# Main.net
KiCad netlist of a schematic drawn in Altium Designer
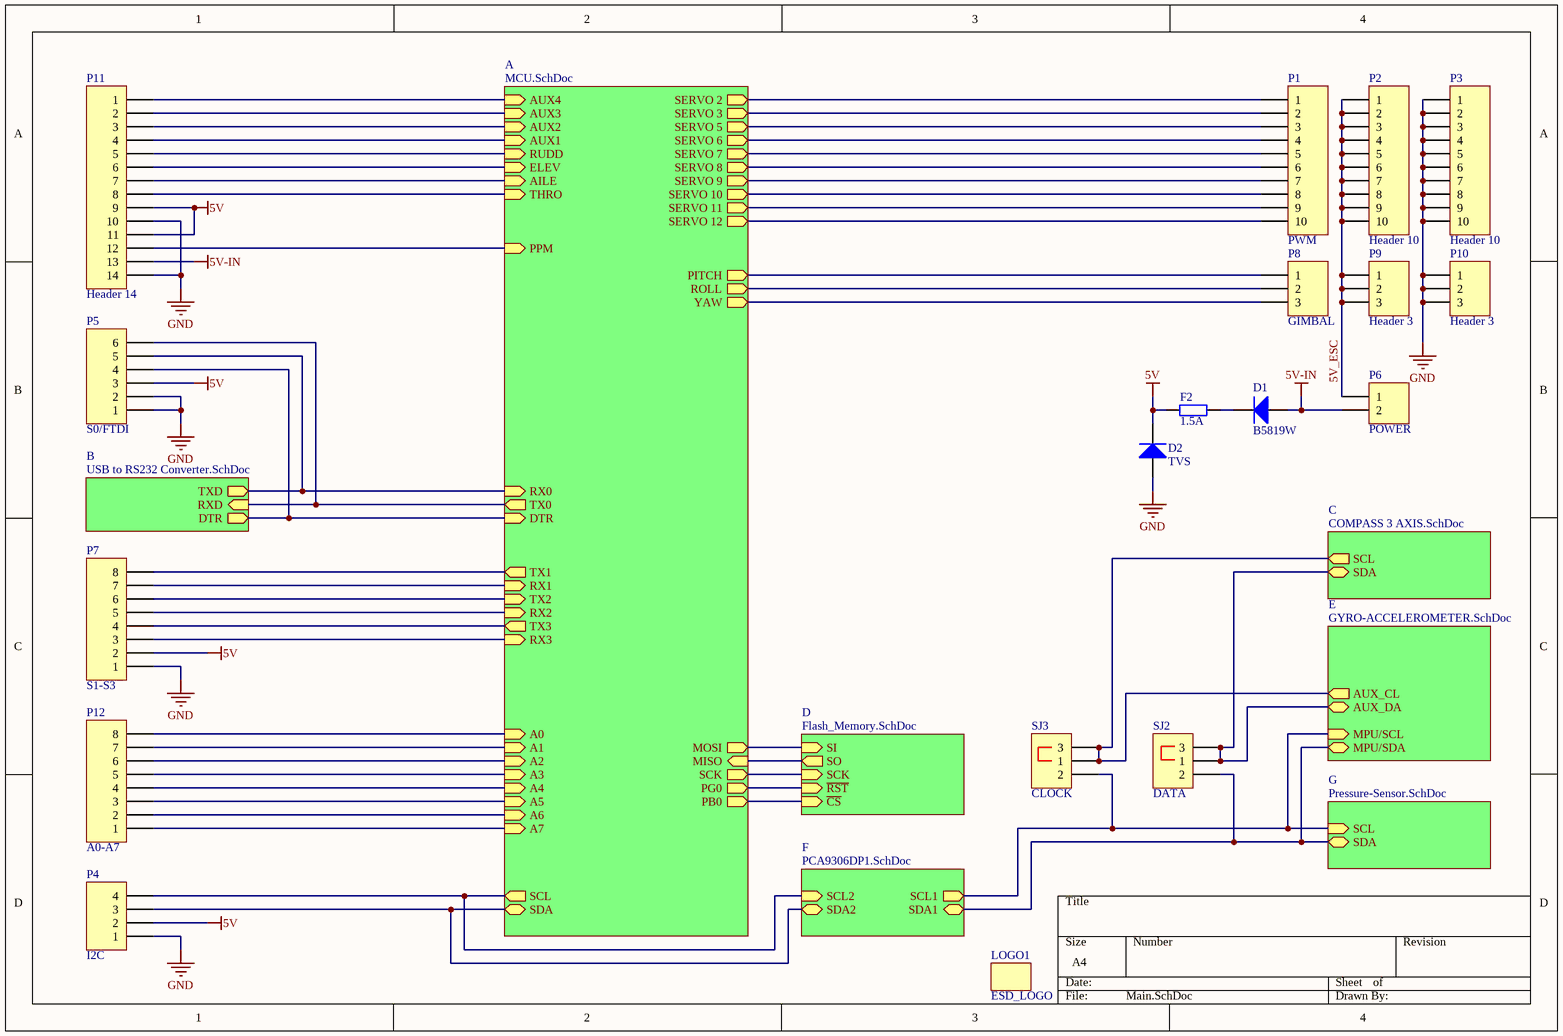
[diagram p0: Main.SchDoc]

(export (version "E")
  (design (tool "Eeschema 10.0.6"))
  (components
    (comp (ref "D1")
      (value "B5819W")
      (footprint "SOD-123")
      (description "Default Diode")
      (fields (field (name "PUBLISHER") "Altium Limited"))
      (libsource (lib "ali_lib") (part "Diode"))
    )
    (comp (ref "D2")
      (value "TVS")
      (footprint "SOD-123")
      (description "Default Diode")
      (fields (field (name "PUBLISHER") "Altium Limited"))
      (libsource (lib "ali_lib") (part "Diode"))
    )
    (comp (ref "F2")
      (value "1.5A")
      (footprint "FUSE_1206(3216)")
      (description "Ferrite Bead")
      (libsource (lib "Miscellaneous Devices") (part "Res2"))
    )
    (comp (ref "LOGO1")
      (value "ESD_LOGO")
      (footprint "LOGO_ESD")
      (libsource (lib "ali_lib") (part "MECHANIC"))
    )
    (comp (ref "P1")
      (value "PWM")
      (footprint "Pin Header 1x10 TH Pitch 2.54mm")
      (description "Header, 10-Pin")
      (fields (field (name "PUBLISHER") "Altium Limited"))
      (libsource (lib "Miscellaneous Connectors") (part "Header 10"))
    )
    (comp (ref "P2")
      (value "Header 10")
      (footprint "Pin Header 1x10 TH Pitch 2.54mm")
      (description "Header, 10-Pin")
      (fields (field (name "PUBLISHER") "Altium Limited"))
      (libsource (lib "Miscellaneous Connectors") (part "Header 10"))
    )
    (comp (ref "P3")
      (value "Header 10")
      (footprint "Pin Header 1x10 TH Pitch 2.54mm")
      (description "Header, 10-Pin")
      (fields (field (name "PUBLISHER") "Altium Limited"))
      (libsource (lib "Miscellaneous Connectors") (part "Header 10"))
    )
    (comp (ref "P4")
      (value "I2C")
      (footprint "MOLEX-CONN-PicoBlade 4POS 1.25MM")
      (description "Header, 4-Pin")
      (libsource (lib "Miscellaneous Connectors") (part "Header 4"))
    )
    (comp (ref "P5")
      (value "S0/FTDI")
      (footprint "MOLEX-CONN-PicoBlade 6POS 1.25MM")
      (description "Header, 6-Pin")
      (libsource (lib "Miscellaneous Connectors") (part "Header 6"))
    )
    (comp (ref "P6")
      (value "POWER")
      (footprint "Pin Header S/M 02x1 TH Pitch 2.54mm")
      (description "Header, 2-Pin")
      (libsource (lib "Miscellaneous Connectors") (part "Header 2"))
    )
    (comp (ref "P7")
      (value "S1-S3")
      (footprint "MOLEX-CONN-PicoBlade 8POS 1.25MM")
      (description "Header, 8-Pin")
      (libsource (lib "Miscellaneous Connectors") (part "Header 8"))
    )
    (comp (ref "P8")
      (value "GIMBAL")
      (footprint "Pin Header 1x3 TH Pitch 2.54mm")
      (description "Header, 3-Pin")
      (fields (field (name "PUBLISHER") "Altium Limited"))
      (libsource (lib "Miscellaneous Connectors") (part "Header 3"))
    )
    (comp (ref "P9")
      (value "Header 3")
      (footprint "Pin Header 1x3 TH Pitch 2.54mm")
      (description "Header, 3-Pin")
      (fields (field (name "PUBLISHER") "Altium Limited"))
      (libsource (lib "Miscellaneous Connectors") (part "Header 3"))
    )
    (comp (ref "P10")
      (value "Header 3")
      (footprint "Pin Header 1x3 TH Pitch 2.54mm")
      (description "Header, 3-Pin")
      (fields (field (name "PUBLISHER") "Altium Limited"))
      (libsource (lib "Miscellaneous Connectors") (part "Header 3"))
    )
    (comp (ref "P11")
      (value "Header 14")
      (footprint "Pin Header 1x14 TH Pitch 2.54mm")
      (description "Header, 14-Pin")
      (fields (field (name "PUBLISHER") "Altium Limited"))
      (libsource (lib "Miscellaneous Connectors") (part "Header 14"))
    )
    (comp (ref "P12")
      (value "A0-A7")
      (footprint "MOLEX-CONN-PicoBlade 8POS 1.25MM")
      (description "Header, 8-Pin")
      (libsource (lib "Miscellaneous Connectors") (part "Header 8"))
    )
    (comp (ref "SJ2")
      (value "DATA")
      (footprint "JUMPER_3")
      (description "Header, 3-Pin")
      (fields (field (name "PUBLISHER") "Altium Limited"))
      (libsource (lib "") (part "Header 3_1"))
    )
    (comp (ref "SJ3")
      (value "CLOCK")
      (footprint "JUMPER_3")
      (description "Header, 3-Pin")
      (fields (field (name "PUBLISHER") "Altium Limited"))
      (libsource (lib "") (part "Header 3_1"))
    )
  )
  (nets
    (net (code "1") (name "/5V_ESC") (class "Default")
      (node (ref "P2") (pin "1") (pinfunction "1_1") (pintype "passive"))
      (node (ref "P2") (pin "10") (pinfunction "10_10") (pintype "passive"))
      (node (ref "P2") (pin "2") (pinfunction "2_2") (pintype "passive"))
      (node (ref "P2") (pin "3") (pinfunction "3_3") (pintype "passive"))
      (node (ref "P2") (pin "4") (pinfunction "4_4") (pintype "passive"))
      (node (ref "P2") (pin "5") (pinfunction "5_5") (pintype "passive"))
      (node (ref "P2") (pin "6") (pinfunction "6_6") (pintype "passive"))
      (node (ref "P2") (pin "7") (pinfunction "7_7") (pintype "passive"))
      (node (ref "P2") (pin "8") (pinfunction "8_8") (pintype "passive"))
      (node (ref "P2") (pin "9") (pinfunction "9_9") (pintype "passive"))
      (node (ref "P6") (pin "1") (pinfunction "1_1") (pintype "passive"))
      (node (ref "P9") (pin "1") (pinfunction "1_1") (pintype "passive"))
      (node (ref "P9") (pin "2") (pinfunction "2_2") (pintype "passive"))
      (node (ref "P9") (pin "3") (pinfunction "3_3") (pintype "passive"))
    )
    (net (code "2") (name "/A0") (class "Default")
      (node (ref "P12") (pin "8") (pinfunction "8_8") (pintype "passive"))
    )
    (net (code "3") (name "/A1") (class "Default")
      (node (ref "P12") (pin "7") (pinfunction "7_7") (pintype "passive"))
    )
    (net (code "4") (name "/A2") (class "Default")
      (node (ref "P12") (pin "6") (pinfunction "6_6") (pintype "passive"))
    )
    (net (code "5") (name "/A3") (class "Default")
      (node (ref "P12") (pin "5") (pinfunction "5_5") (pintype "passive"))
    )
    (net (code "6") (name "/A4") (class "Default")
      (node (ref "P12") (pin "4") (pinfunction "4_4") (pintype "passive"))
    )
    (net (code "7") (name "/A5") (class "Default")
      (node (ref "P12") (pin "3") (pinfunction "3_3") (pintype "passive"))
    )
    (net (code "8") (name "/A6") (class "Default")
      (node (ref "P12") (pin "2") (pinfunction "2_2") (pintype "passive"))
    )
    (net (code "9") (name "/A7") (class "Default")
      (node (ref "P12") (pin "1") (pinfunction "1_1") (pintype "passive"))
    )
    (net (code "10") (name "/AILE") (class "Default")
      (node (ref "P11") (pin "7") (pinfunction "7_7") (pintype "passive"))
    )
    (net (code "11") (name "/AUX1") (class "Default")
      (node (ref "P11") (pin "4") (pinfunction "4_4") (pintype "passive"))
    )
    (net (code "12") (name "/AUX2") (class "Default")
      (node (ref "P11") (pin "3") (pinfunction "3_3") (pintype "passive"))
    )
    (net (code "13") (name "/AUX3") (class "Default")
      (node (ref "P11") (pin "2") (pinfunction "2_2") (pintype "passive"))
    )
    (net (code "14") (name "/AUX4") (class "Default")
      (node (ref "P11") (pin "1") (pinfunction "1_1") (pintype "passive"))
    )
    (net (code "15") (name "/AUX_CL") (class "Default")
      (node (ref "SJ3") (pin "1") (pinfunction "1_1") (pintype "passive"))
      (node (ref "SJ3") (pin "3") (pinfunction "3_3") (pintype "passive"))
    )
    (net (code "16") (name "/AUX_DA") (class "Default")
      (node (ref "SJ2") (pin "1") (pinfunction "1_1") (pintype "passive"))
      (node (ref "SJ2") (pin "3") (pinfunction "3_3") (pintype "passive"))
    )
    (net (code "17") (name "/DTR") (class "Default")
      (node (ref "P5") (pin "4") (pinfunction "4_4") (pintype "passive"))
    )
    (net (code "18") (name "/ELEV") (class "Default")
      (node (ref "P11") (pin "6") (pinfunction "6_6") (pintype "passive"))
    )
    (net (code "20") (name "/MPU{slash}SDA") (class "Default")
      (node (ref "SJ2") (pin "2") (pinfunction "2_2") (pintype "passive"))
    )
    (net (code "23") (name "/PITCH") (class "Default")
      (node (ref "P8") (pin "1") (pinfunction "1_1") (pintype "passive"))
    )
    (net (code "24") (name "/PPM") (class "Default")
      (node (ref "P11") (pin "12") (pinfunction "12_12") (pintype "passive"))
    )
    (net (code "25") (name "/ROLL") (class "Default")
      (node (ref "P8") (pin "2") (pinfunction "2_2") (pintype "passive"))
    )
    (net (code "26") (name "/RUDD") (class "Default")
      (node (ref "P11") (pin "5") (pinfunction "5_5") (pintype "passive"))
    )
    (net (code "27") (name "/RX1") (class "Default")
      (node (ref "P7") (pin "7") (pinfunction "7_7") (pintype "passive"))
    )
    (net (code "28") (name "/RX2") (class "Default")
      (node (ref "P7") (pin "5") (pinfunction "5_5") (pintype "passive"))
    )
    (net (code "29") (name "/RX3") (class "Default")
      (node (ref "P7") (pin "3") (pinfunction "3_3") (pintype "passive"))
    )
    (net (code "31") (name "/SCL") (class "Default")
      (node (ref "P4") (pin "4") (pinfunction "4_4") (pintype "passive"))
    )
    (net (code "32") (name "/SCL1") (class "Default")
      (node (ref "SJ3") (pin "2") (pinfunction "2_2") (pintype "passive"))
    )
    (net (code "33") (name "/SDA") (class "Default")
      (node (ref "P4") (pin "3") (pinfunction "3_3") (pintype "passive"))
    )
    (net (code "34") (name "/SERVO 2") (class "Default")
      (node (ref "P1") (pin "1") (pinfunction "1_1") (pintype "passive"))
    )
    (net (code "35") (name "/SERVO 3") (class "Default")
      (node (ref "P1") (pin "2") (pinfunction "2_2") (pintype "passive"))
    )
    (net (code "36") (name "/SERVO 5") (class "Default")
      (node (ref "P1") (pin "3") (pinfunction "3_3") (pintype "passive"))
    )
    (net (code "37") (name "/SERVO 6") (class "Default")
      (node (ref "P1") (pin "4") (pinfunction "4_4") (pintype "passive"))
    )
    (net (code "38") (name "/SERVO 7") (class "Default")
      (node (ref "P1") (pin "5") (pinfunction "5_5") (pintype "passive"))
    )
    (net (code "39") (name "/SERVO 8") (class "Default")
      (node (ref "P1") (pin "6") (pinfunction "6_6") (pintype "passive"))
    )
    (net (code "40") (name "/SERVO 9") (class "Default")
      (node (ref "P1") (pin "7") (pinfunction "7_7") (pintype "passive"))
    )
    (net (code "41") (name "/SERVO 10") (class "Default")
      (node (ref "P1") (pin "8") (pinfunction "8_8") (pintype "passive"))
    )
    (net (code "42") (name "/SERVO 11") (class "Default")
      (node (ref "P1") (pin "9") (pinfunction "9_9") (pintype "passive"))
    )
    (net (code "43") (name "/SERVO 12") (class "Default")
      (node (ref "P1") (pin "10") (pinfunction "10_10") (pintype "passive"))
    )
    (net (code "45") (name "/THRO") (class "Default")
      (node (ref "P11") (pin "8") (pinfunction "8_8") (pintype "passive"))
    )
    (net (code "46") (name "/TX0") (class "Default")
      (node (ref "P5") (pin "6") (pinfunction "6_6") (pintype "passive"))
    )
    (net (code "47") (name "/TX1") (class "Default")
      (node (ref "P7") (pin "8") (pinfunction "8_8") (pintype "passive"))
    )
    (net (code "48") (name "/TX2") (class "Default")
      (node (ref "P7") (pin "6") (pinfunction "6_6") (pintype "passive"))
    )
    (net (code "49") (name "/TX3") (class "Default")
      (node (ref "P7") (pin "4") (pinfunction "4_4") (pintype "passive"))
    )
    (net (code "50") (name "/TXD") (class "Default")
      (node (ref "P5") (pin "5") (pinfunction "5_5") (pintype "passive"))
    )
    (net (code "51") (name "/YAW") (class "Default")
      (node (ref "P8") (pin "3") (pinfunction "3_3") (pintype "passive"))
    )
    (net (code "52") (name "5V") (class "Default")
      (node (ref "D2") (pin "1") (pinfunction "A_1") (pintype "passive"))
      (node (ref "F2") (pin "2") (pinfunction "2_2") (pintype "passive"))
      (node (ref "P11") (pin "11") (pinfunction "11_11") (pintype "passive"))
      (node (ref "P11") (pin "9") (pinfunction "9_9") (pintype "passive"))
      (node (ref "P4") (pin "2") (pinfunction "2_2") (pintype "passive"))
      (node (ref "P5") (pin "3") (pinfunction "3_3") (pintype "passive"))
      (node (ref "P7") (pin "2") (pinfunction "2_2") (pintype "passive"))
    )
    (net (code "53") (name "5V-IN") (class "Default")
      (node (ref "D1") (pin "2") (pinfunction "K_2") (pintype "passive"))
      (node (ref "P11") (pin "13") (pinfunction "13_13") (pintype "passive"))
      (node (ref "P6") (pin "2") (pinfunction "2_2") (pintype "passive"))
    )
    (net (code "54") (name "GND") (class "Default")
      (node (ref "D2") (pin "2") (pinfunction "K_2") (pintype "passive"))
      (node (ref "P10") (pin "1") (pinfunction "1_1") (pintype "passive"))
      (node (ref "P10") (pin "2") (pinfunction "2_2") (pintype "passive"))
      (node (ref "P10") (pin "3") (pinfunction "3_3") (pintype "passive"))
      (node (ref "P11") (pin "10") (pinfunction "10_10") (pintype "passive"))
      (node (ref "P11") (pin "14") (pinfunction "14_14") (pintype "passive"))
      (node (ref "P3") (pin "1") (pinfunction "1_1") (pintype "passive"))
      (node (ref "P3") (pin "10") (pinfunction "10_10") (pintype "passive"))
      (node (ref "P3") (pin "2") (pinfunction "2_2") (pintype "passive"))
      (node (ref "P3") (pin "3") (pinfunction "3_3") (pintype "passive"))
      (node (ref "P3") (pin "4") (pinfunction "4_4") (pintype "passive"))
      (node (ref "P3") (pin "5") (pinfunction "5_5") (pintype "passive"))
      (node (ref "P3") (pin "6") (pinfunction "6_6") (pintype "passive"))
      (node (ref "P3") (pin "7") (pinfunction "7_7") (pintype "passive"))
      (node (ref "P3") (pin "8") (pinfunction "8_8") (pintype "passive"))
      (node (ref "P3") (pin "9") (pinfunction "9_9") (pintype "passive"))
      (node (ref "P4") (pin "1") (pinfunction "1_1") (pintype "passive"))
      (node (ref "P5") (pin "1") (pinfunction "1_1") (pintype "passive"))
      (node (ref "P5") (pin "2") (pinfunction "2_2") (pintype "passive"))
      (node (ref "P7") (pin "1") (pinfunction "1_1") (pintype "passive"))
    )
    (net (code "55") (name "Net-(D1-A)") (class "Default")
      (node (ref "D1") (pin "1") (pinfunction "A_1") (pintype "passive"))
      (node (ref "F2") (pin "1") (pinfunction "1_1") (pintype "passive"))
    )
  )
)
